# Backside.net
KiCad netlist of a schematic drawn in Altium Designer
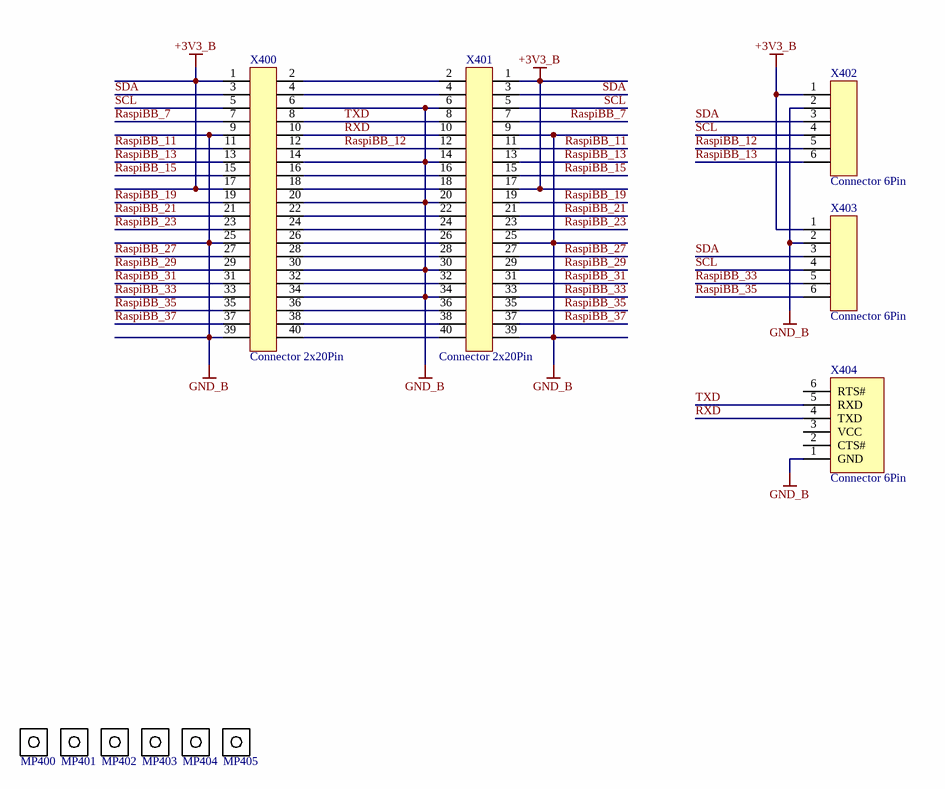
[diagram p0: Backside.SchDoc]

(export (version "E")
  (design (tool "Eeschema 10.0.6"))
  (components
    (comp (ref "MP400")
      (value "Mounting Hole")
      (footprint "M2 2.3")
      (description "Different Mounting holes")
      (libsource (lib "Cyberdeck") (part "MP_Mounting Hole"))
    )
    (comp (ref "MP401")
      (value "Mounting Hole")
      (footprint "M2 2.3")
      (description "Different Mounting holes")
      (libsource (lib "Cyberdeck") (part "MP_Mounting Hole"))
    )
    (comp (ref "MP402")
      (value "Mounting Hole")
      (footprint "M2 2.3")
      (description "Different Mounting holes")
      (libsource (lib "Cyberdeck") (part "MP_Mounting Hole"))
    )
    (comp (ref "MP403")
      (value "Mounting Hole")
      (footprint "M2 2.3")
      (description "Different Mounting holes")
      (libsource (lib "Cyberdeck") (part "MP_Mounting Hole"))
    )
    (comp (ref "MP404")
      (value "Mounting Hole")
      (footprint "M2 2.3")
      (description "Different Mounting holes")
      (libsource (lib "Cyberdeck") (part "MP_Mounting Hole"))
    )
    (comp (ref "MP405")
      (value "Mounting Hole")
      (footprint "M2 2.3")
      (description "Different Mounting holes")
      (libsource (lib "Cyberdeck") (part "MP_Mounting Hole"))
    )
    (comp (ref "X400")
      (value "Connector 2x20Pin")
      (footprint "Pin Header 2x20 TH Pitch 2.54mm - sh")
      (description "Generic connector 2x20 Pin")
      (libsource (lib "CyberDeck") (part "X_Connector 2x20Pin"))
    )
    (comp (ref "X401")
      (value "Connector 2x20Pin")
      (footprint "Pin Header 2x20 TH Pitch 2.54mm - sh")
      (description "Generic connector 2x20 Pin")
      (libsource (lib "") (part "X_Connector 2x20Pin_1"))
    )
    (comp (ref "X402")
      (value "Connector 6Pin")
      (footprint "Pin Header 2x3 TH Pitch 2.54mm f")
      (description "Generic connector 6 Pin")
      (libsource (lib "Cyberdeck") (part "X_Connector 6Pin"))
    )
    (comp (ref "X403")
      (value "Connector 6Pin")
      (footprint "Pin Header 2x3 TH Pitch 2.54mm f")
      (description "Generic connector 6 Pin")
      (libsource (lib "Cyberdeck") (part "X_Connector 6Pin"))
    )
    (comp (ref "X404")
      (value "Connector 6Pin")
      (footprint "Pin Header 1x6 TH Pitch 2.54mm")
      (description "Connector 6 Pin for FTDI cable")
      (fields
        (field (name "MANUFACTURER") "Mill-Max")
        (field (name "MANUFACTURER PART NUMBER") "419-10-206-00-006000")
      )
      (libsource (lib "CyberDeck") (part "X_Connector FTDI cable"))
    )
  )
  (nets
    (net (code "1") (name "+3V3_B") (class "Default")
      (node (ref "X400") (pin "1") (pintype "passive"))
      (node (ref "X400") (pin "17") (pintype "passive"))
      (node (ref "X401") (pin "1") (pintype "passive"))
      (node (ref "X401") (pin "17") (pintype "passive"))
      (node (ref "X402") (pin "1") (pintype "passive"))
      (node (ref "X403") (pin "1") (pintype "passive"))
    )
    (net (code "2") (name "/RXD") (class "Default")
      (node (ref "X400") (pin "10") (pintype "passive"))
      (node (ref "X401") (pin "10") (pintype "passive"))
      (node (ref "X404") (pin "4") (pinfunction "TXD_4") (pintype "passive"))
    )
    (net (code "3") (name "/RaspiBB_7") (class "Default")
      (node (ref "X400") (pin "7") (pintype "passive"))
      (node (ref "X401") (pin "7") (pintype "passive"))
    )
    (net (code "4") (name "/RaspiBB_11") (class "Default")
      (node (ref "X400") (pin "11") (pintype "passive"))
      (node (ref "X401") (pin "11") (pintype "passive"))
    )
    (net (code "5") (name "/RaspiBB_12") (class "Default")
      (node (ref "X400") (pin "12") (pintype "passive"))
      (node (ref "X401") (pin "12") (pintype "passive"))
      (node (ref "X402") (pin "5") (pintype "passive"))
    )
    (net (code "6") (name "/RaspiBB_13") (class "Default")
      (node (ref "X400") (pin "13") (pintype "passive"))
      (node (ref "X401") (pin "13") (pintype "passive"))
      (node (ref "X402") (pin "6") (pintype "passive"))
    )
    (net (code "7") (name "/RaspiBB_15") (class "Default")
      (node (ref "X400") (pin "15") (pintype "passive"))
      (node (ref "X401") (pin "15") (pintype "passive"))
    )
    (net (code "8") (name "/RaspiBB_19") (class "Default")
      (node (ref "X400") (pin "19") (pintype "passive"))
      (node (ref "X401") (pin "19") (pintype "passive"))
    )
    (net (code "9") (name "/RaspiBB_21") (class "Default")
      (node (ref "X400") (pin "21") (pintype "passive"))
      (node (ref "X401") (pin "21") (pintype "passive"))
    )
    (net (code "10") (name "/RaspiBB_23") (class "Default")
      (node (ref "X400") (pin "23") (pintype "passive"))
      (node (ref "X401") (pin "23") (pintype "passive"))
    )
    (net (code "11") (name "/RaspiBB_27") (class "Default")
      (node (ref "X400") (pin "27") (pintype "passive"))
      (node (ref "X401") (pin "27") (pintype "passive"))
    )
    (net (code "12") (name "/RaspiBB_29") (class "Default")
      (node (ref "X400") (pin "29") (pintype "passive"))
      (node (ref "X401") (pin "29") (pintype "passive"))
    )
    (net (code "13") (name "/RaspiBB_31") (class "Default")
      (node (ref "X400") (pin "31") (pintype "passive"))
      (node (ref "X401") (pin "31") (pintype "passive"))
    )
    (net (code "14") (name "/RaspiBB_33") (class "Default")
      (node (ref "X400") (pin "33") (pintype "passive"))
      (node (ref "X401") (pin "33") (pintype "passive"))
      (node (ref "X403") (pin "5") (pintype "passive"))
    )
    (net (code "15") (name "/RaspiBB_35") (class "Default")
      (node (ref "X400") (pin "35") (pintype "passive"))
      (node (ref "X401") (pin "35") (pintype "passive"))
      (node (ref "X403") (pin "6") (pintype "passive"))
    )
    (net (code "16") (name "/RaspiBB_37") (class "Default")
      (node (ref "X400") (pin "37") (pintype "passive"))
      (node (ref "X401") (pin "37") (pintype "passive"))
    )
    (net (code "17") (name "/SCL") (class "Default")
      (node (ref "X400") (pin "5") (pintype "passive"))
      (node (ref "X401") (pin "5") (pintype "passive"))
      (node (ref "X402") (pin "4") (pintype "passive"))
      (node (ref "X403") (pin "4") (pintype "passive"))
    )
    (net (code "18") (name "/SDA") (class "Default")
      (node (ref "X400") (pin "3") (pintype "passive"))
      (node (ref "X401") (pin "3") (pintype "passive"))
      (node (ref "X402") (pin "3") (pintype "passive"))
      (node (ref "X403") (pin "3") (pintype "passive"))
    )
    (net (code "19") (name "/TXD") (class "Default")
      (node (ref "X400") (pin "8") (pintype "passive"))
      (node (ref "X401") (pin "8") (pintype "passive"))
      (node (ref "X404") (pin "5") (pinfunction "RXD_5") (pintype "passive"))
    )
    (net (code "20") (name "GND_B") (class "Default")
      (node (ref "X400") (pin "14") (pintype "passive"))
      (node (ref "X400") (pin "20") (pintype "passive"))
      (node (ref "X400") (pin "25") (pintype "passive"))
      (node (ref "X400") (pin "30") (pintype "passive"))
      (node (ref "X400") (pin "34") (pintype "passive"))
      (node (ref "X400") (pin "39") (pintype "passive"))
      (node (ref "X400") (pin "6") (pintype "passive"))
      (node (ref "X400") (pin "9") (pintype "passive"))
      (node (ref "X401") (pin "14") (pintype "passive"))
      (node (ref "X401") (pin "20") (pintype "passive"))
      (node (ref "X401") (pin "25") (pintype "passive"))
      (node (ref "X401") (pin "30") (pintype "passive"))
      (node (ref "X401") (pin "34") (pintype "passive"))
      (node (ref "X401") (pin "39") (pintype "passive"))
      (node (ref "X401") (pin "6") (pintype "passive"))
      (node (ref "X401") (pin "9") (pintype "passive"))
      (node (ref "X402") (pin "2") (pintype "passive"))
      (node (ref "X403") (pin "2") (pintype "passive"))
      (node (ref "X404") (pin "1") (pinfunction "GND_1") (pintype "passive"))
    )
    (net (code "21") (name "Net-(X400-Pad2)") (class "Default")
      (node (ref "X400") (pin "2") (pintype "passive"))
      (node (ref "X401") (pin "2") (pintype "passive"))
    )
    (net (code "22") (name "Net-(X400-Pad4)") (class "Default")
      (node (ref "X400") (pin "4") (pintype "passive"))
      (node (ref "X401") (pin "4") (pintype "passive"))
    )
    (net (code "23") (name "Net-(X400-Pad16)") (class "Default")
      (node (ref "X400") (pin "16") (pintype "passive"))
      (node (ref "X401") (pin "16") (pintype "passive"))
    )
    (net (code "24") (name "Net-(X400-Pad18)") (class "Default")
      (node (ref "X400") (pin "18") (pintype "passive"))
      (node (ref "X401") (pin "18") (pintype "passive"))
    )
    (net (code "25") (name "Net-(X400-Pad22)") (class "Default")
      (node (ref "X400") (pin "22") (pintype "passive"))
      (node (ref "X401") (pin "22") (pintype "passive"))
    )
    (net (code "26") (name "Net-(X400-Pad24)") (class "Default")
      (node (ref "X400") (pin "24") (pintype "passive"))
      (node (ref "X401") (pin "24") (pintype "passive"))
    )
    (net (code "27") (name "Net-(X400-Pad26)") (class "Default")
      (node (ref "X400") (pin "26") (pintype "passive"))
      (node (ref "X401") (pin "26") (pintype "passive"))
    )
    (net (code "28") (name "Net-(X400-Pad28)") (class "Default")
      (node (ref "X400") (pin "28") (pintype "passive"))
      (node (ref "X401") (pin "28") (pintype "passive"))
    )
    (net (code "29") (name "Net-(X400-Pad32)") (class "Default")
      (node (ref "X400") (pin "32") (pintype "passive"))
      (node (ref "X401") (pin "32") (pintype "passive"))
    )
    (net (code "30") (name "Net-(X400-Pad36)") (class "Default")
      (node (ref "X400") (pin "36") (pintype "passive"))
      (node (ref "X401") (pin "36") (pintype "passive"))
    )
    (net (code "31") (name "Net-(X400-Pad38)") (class "Default")
      (node (ref "X400") (pin "38") (pintype "passive"))
      (node (ref "X401") (pin "38") (pintype "passive"))
    )
    (net (code "32") (name "Net-(X400-Pad40)") (class "Default")
      (node (ref "X400") (pin "40") (pintype "passive"))
      (node (ref "X401") (pin "40") (pintype "passive"))
    )
    (net (code "33") (name "unconnected-(X404-CTS#-Pad2)") (class "Default")
      (node (ref "X404") (pin "2") (pinfunction "CTS#_2") (pintype "passive"))
    )
    (net (code "34") (name "unconnected-(X404-RTS#-Pad6)") (class "Default")
      (node (ref "X404") (pin "6") (pinfunction "RTS#_6") (pintype "passive"))
    )
    (net (code "35") (name "unconnected-(X404-VCC-Pad3)") (class "Default")
      (node (ref "X404") (pin "3") (pinfunction "VCC_3") (pintype "passive"))
    )
  )
)
